# APD9328_ANALOG.net
KiCad netlist of a schematic drawn in Altium Designer
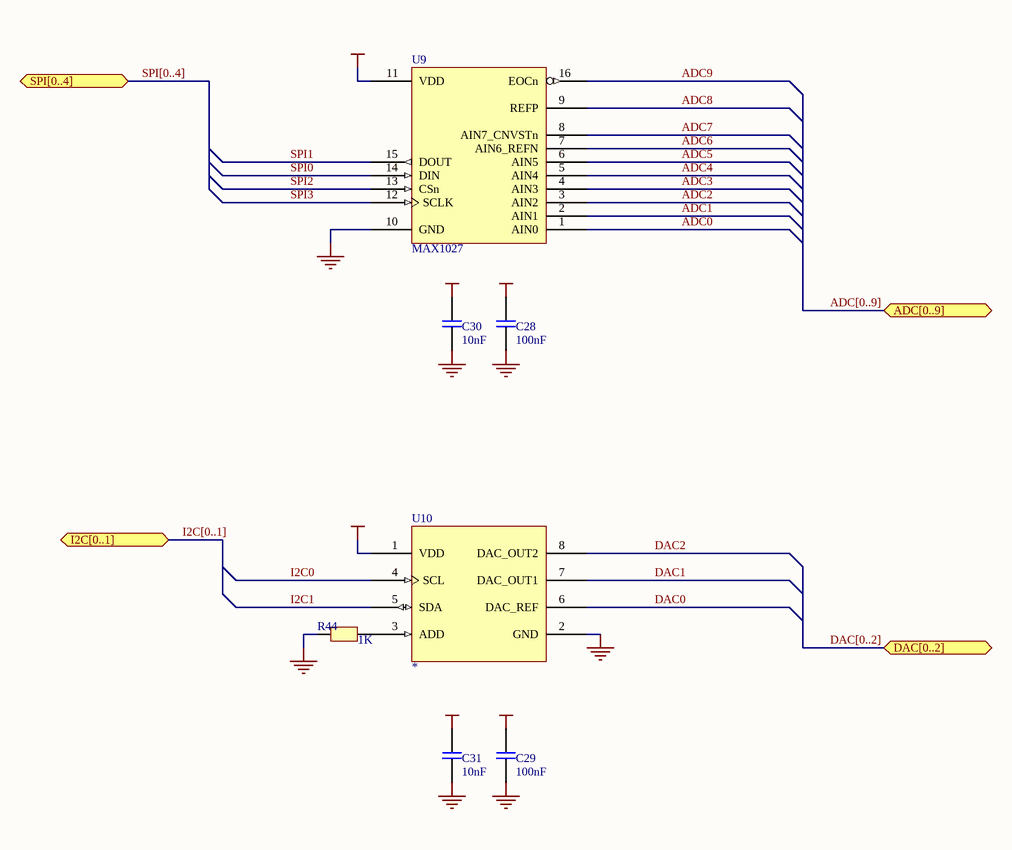
[diagram p0: APD9328_ANALOG.SchDoc]

(export (version "E")
  (design (tool "Eeschema 10.0.6"))
  (components
    (comp (ref "C28") (value "100nF") (footprint "0402") (libsource (lib "Misc") (part "Cap")))
    (comp (ref "C29") (value "100nF") (footprint "0402") (libsource (lib "Misc") (part "Cap")))
    (comp (ref "C30") (value "10nF") (footprint "0402") (libsource (lib "Misc") (part "Cap")))
    (comp (ref "C31") (value "10nF") (footprint "0402") (libsource (lib "Misc") (part "Cap")))
    (comp (ref "R44") (value "1K") (footprint "0402") (libsource (lib "*") (part "Res")))
    (comp (ref "U9")
      (value "MAX1027")
      (footprint "QSOP16")
      (description "ADC serial converter")
      (fields (field (name "MANUFACTURER") "Maxim") (field (name "PART NUMBER") "MAX1027-BCCE"))
      (libsource (lib "*") (part "MAX1027"))
    )
    (comp (ref "U10") (value "*") (libsource (lib "Armadeus") (part "MAX5821")))
  )
  (nets
    (net (code "2") (name "+3V3") (class "Default")
      (node (ref "C28") (pin "2") (pintype "passive"))
      (node (ref "C29") (pin "2") (pintype "passive"))
      (node (ref "C30") (pin "2") (pintype "passive"))
      (node (ref "C31") (pin "2") (pintype "passive"))
      (node (ref "U10") (pin "1") (pinfunction "VDD_1") (pintype "power_in"))
      (node (ref "U9") (pin "11") (pinfunction "VDD_11") (pintype "power_in"))
    )
    (net (code "3") (name "/ADC0") (class "Default")
      (node (ref "U9") (pin "1") (pinfunction "AIN0_1") (pintype "passive"))
    )
    (net (code "4") (name "/ADC1") (class "Default")
      (node (ref "U9") (pin "2") (pinfunction "AIN1_2") (pintype "passive"))
    )
    (net (code "5") (name "/ADC2") (class "Default")
      (node (ref "U9") (pin "3") (pinfunction "AIN2_3") (pintype "passive"))
    )
    (net (code "6") (name "/ADC3") (class "Default")
      (node (ref "U9") (pin "4") (pinfunction "AIN3_4") (pintype "passive"))
    )
    (net (code "7") (name "/ADC4") (class "Default")
      (node (ref "U9") (pin "5") (pinfunction "AIN4_5") (pintype "passive"))
    )
    (net (code "8") (name "/ADC5") (class "Default")
      (node (ref "U9") (pin "6") (pinfunction "AIN5_6") (pintype "passive"))
    )
    (net (code "9") (name "/ADC6") (class "Default")
      (node (ref "U9") (pin "7") (pinfunction "AIN6_REFN_7") (pintype "passive"))
    )
    (net (code "10") (name "/ADC7") (class "Default")
      (node (ref "U9") (pin "8") (pinfunction "AIN7_CNVSTn_8") (pintype "passive"))
    )
    (net (code "11") (name "/ADC8") (class "Default")
      (node (ref "U9") (pin "9") (pinfunction "REFP_9") (pintype "passive"))
    )
    (net (code "12") (name "/ADC9") (class "Default")
      (node (ref "U9") (pin "16") (pinfunction "EOCn_16") (pintype "output"))
    )
    (net (code "14") (name "/DAC0") (class "Default")
      (node (ref "U10") (pin "6") (pinfunction "DAC_REF_6") (pintype "passive"))
    )
    (net (code "15") (name "/DAC1") (class "Default")
      (node (ref "U10") (pin "7") (pinfunction "DAC_OUT1_7") (pintype "passive"))
    )
    (net (code "16") (name "/DAC2") (class "Default")
      (node (ref "U10") (pin "8") (pinfunction "DAC_OUT2_8") (pintype "passive"))
    )
    (net (code "18") (name "/I2C0") (class "Default")
      (node (ref "U10") (pin "4") (pinfunction "SCL_4") (pintype "input"))
    )
    (net (code "19") (name "/I2C1") (class "Default")
      (node (ref "U10") (pin "5") (pinfunction "SDA_5") (pintype "bidirectional"))
    )
    (net (code "21") (name "/SPI0") (class "Default")
      (node (ref "U9") (pin "14") (pinfunction "DIN_14") (pintype "input"))
    )
    (net (code "22") (name "/SPI1") (class "Default")
      (node (ref "U9") (pin "15") (pinfunction "DOUT_15") (pintype "output"))
    )
    (net (code "23") (name "/SPI2") (class "Default")
      (node (ref "U9") (pin "13") (pinfunction "CSn_13") (pintype "input"))
    )
    (net (code "24") (name "/SPI3") (class "Default")
      (node (ref "U9") (pin "12") (pinfunction "SCLK_12") (pintype "input"))
    )
    (net (code "26") (name "GND") (class "Default")
      (node (ref "C28") (pin "1") (pintype "passive"))
      (node (ref "C29") (pin "1") (pintype "passive"))
      (node (ref "C30") (pin "1") (pintype "passive"))
      (node (ref "C31") (pin "1") (pintype "passive"))
      (node (ref "R44") (pin "1") (pintype "passive"))
      (node (ref "U10") (pin "2") (pinfunction "GND_2") (pintype "power_in"))
      (node (ref "U9") (pin "10") (pinfunction "GND_10") (pintype "power_in"))
    )
    (net (code "27") (name "Net-(U10-ADD)") (class "Default")
      (node (ref "R44") (pin "2") (pintype "passive"))
      (node (ref "U10") (pin "3") (pinfunction "ADD_3") (pintype "input"))
    )
  )
)
